# mk2.net
KiCad netlist of a schematic drawn in EAGLE
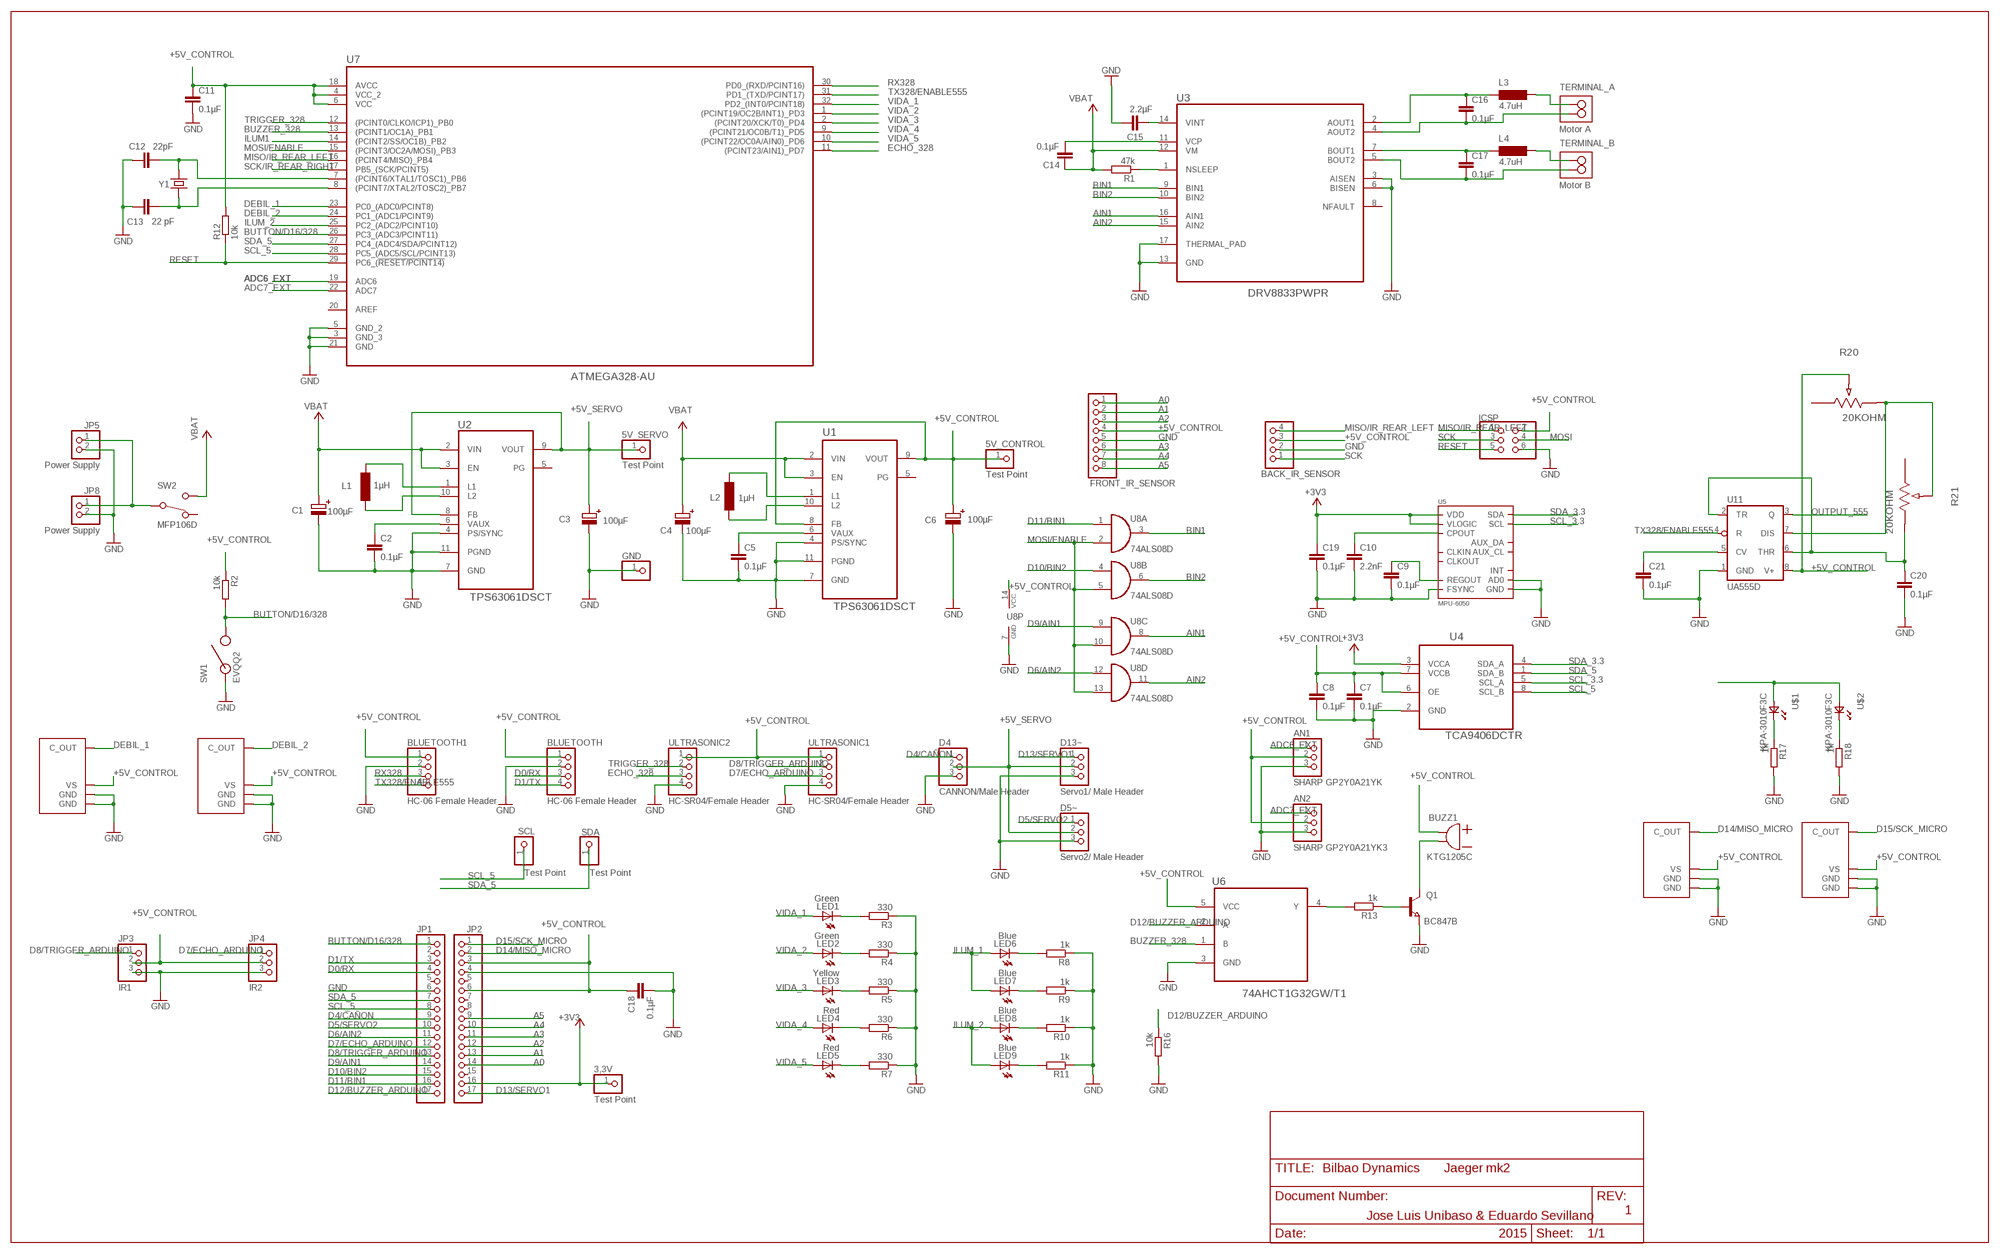
[diagram p0: schematic, sheet 1]

(export (version "E")
  (design (tool "Eeschema 10.0.6"))
  (components
    (comp (ref "3,3V")
      (value "Test Point")
      (footprint "eagle-import:1X01")
      (libsource (lib "eagle-import") (part "PINHD-1X1"))
    )
    (comp (ref "5V_CONTROL")
      (value "Test Point")
      (footprint "eagle-import:1X01")
      (libsource (lib "eagle-import") (part "PINHD-1X1"))
    )
    (comp (ref "5V_SERVO")
      (value "Test Point")
      (footprint "eagle-import:1X01")
      (libsource (lib "eagle-import") (part "PINHD-1X1"))
    )
    (comp (ref "AN1")
      (value "SHARP GP2Y0A21YK")
      (footprint "eagle-import:1X03")
      (libsource (lib "eagle-import") (part "PINHD-1X3"))
    )
    (comp (ref "AN2")
      (value "SHARP GP2Y0A21YK3")
      (footprint "eagle-import:1X03")
      (libsource (lib "eagle-import") (part "PINHD-1X3"))
    )
    (comp (ref "BACK_IR_SENSOR")
      (value "PINHD-1X4")
      (footprint "eagle-import:1X04")
      (libsource (lib "eagle-import") (part "PINHD-1X4"))
    )
    (comp (ref "BLUETOOTH")
      (value "HC-06 Female Header")
      (footprint "eagle-import:1X04")
      (libsource (lib "eagle-import") (part "PINHD-1X4"))
    )
    (comp (ref "BLUETOOTH1")
      (value "HC-06 Female Header")
      (footprint "eagle-import:1X04")
      (libsource (lib "eagle-import") (part "PINHD-1X4"))
    )
    (comp (ref "BUZZ1")
      (value "KTG1205C")
      (footprint "eagle-import:KTG1205C")
      (libsource (lib "eagle-import") (part "KTG1205C"))
    )
    (comp (ref "C1")
      (value "100µF")
      (footprint "eagle-import:EDK107M016A9G")
      (libsource (lib "eagle-import") (part "EDK107M016A9G"))
    )
    (comp (ref "C2")
      (value "0.1µF")
      (footprint "eagle-import:C0805K")
      (libsource (lib "eagle-import") (part "C-EUC0805K"))
    )
    (comp (ref "C3")
      (value "100µF")
      (footprint "eagle-import:EDK107M016A9G")
      (libsource (lib "eagle-import") (part "EDK107M016A9G"))
    )
    (comp (ref "C4")
      (value "100µF")
      (footprint "eagle-import:EDK107M016A9G")
      (libsource (lib "eagle-import") (part "EDK107M016A9G"))
    )
    (comp (ref "C5")
      (value "0.1µF")
      (footprint "eagle-import:C0805K")
      (libsource (lib "eagle-import") (part "C-EUC0805K"))
    )
    (comp (ref "C6")
      (value "100µF")
      (footprint "eagle-import:EDK107M016A9G")
      (libsource (lib "eagle-import") (part "EDK107M016A9G"))
    )
    (comp (ref "C7")
      (value "0.1µF")
      (footprint "eagle-import:C0805")
      (libsource (lib "eagle-import") (part "C-EUC0805"))
    )
    (comp (ref "C8")
      (value "0.1µF")
      (footprint "eagle-import:C0805")
      (libsource (lib "eagle-import") (part "C-EUC0805"))
    )
    (comp (ref "C9")
      (value "0.1µF")
      (footprint "eagle-import:C0805")
      (libsource (lib "eagle-import") (part "C-EUC0805"))
    )
    (comp (ref "C10")
      (value "2.2nF")
      (footprint "eagle-import:C0805")
      (libsource (lib "eagle-import") (part "C-EUC0805"))
    )
    (comp (ref "C11")
      (value "0.1µF")
      (footprint "eagle-import:C0805K")
      (libsource (lib "eagle-import") (part "C-EUC0805K"))
    )
    (comp (ref "C12")
      (value "22pF")
      (footprint "eagle-import:C0805K")
      (libsource (lib "eagle-import") (part "C-EUC0805K"))
    )
    (comp (ref "C13")
      (value "22 pF")
      (footprint "eagle-import:C0805K")
      (libsource (lib "eagle-import") (part "C-EUC0805K"))
    )
    (comp (ref "C14")
      (value "0.1µF")
      (footprint "eagle-import:C0805")
      (libsource (lib "eagle-import") (part "C-EUC0805"))
    )
    (comp (ref "C15")
      (value "2.2µF")
      (footprint "eagle-import:C0805")
      (libsource (lib "eagle-import") (part "C-EUC0805"))
    )
    (comp (ref "C16")
      (value "0.1µF")
      (footprint "eagle-import:C0805")
      (libsource (lib "eagle-import") (part "C-EUC0805"))
    )
    (comp (ref "C17")
      (value "0.1µF")
      (footprint "eagle-import:C0805")
      (libsource (lib "eagle-import") (part "C-EUC0805"))
    )
    (comp (ref "C18")
      (value "0.1µF")
      (footprint "eagle-import:C0805")
      (libsource (lib "eagle-import") (part "C-EUC0805"))
    )
    (comp (ref "C19")
      (value "0.1µF")
      (footprint "eagle-import:C0805")
      (libsource (lib "eagle-import") (part "C-EUC0805"))
    )
    (comp (ref "C20")
      (value "0.1µF")
      (footprint "eagle-import:C0805")
      (libsource (lib "eagle-import") (part "C-EUC0805"))
    )
    (comp (ref "C21")
      (value "0.1µF")
      (footprint "eagle-import:C0805")
      (libsource (lib "eagle-import") (part "C-EUC0805"))
    )
    (comp (ref "D4")
      (value "CANNON/Male Header")
      (footprint "eagle-import:1X03")
      (libsource (lib "eagle-import") (part "PINHD-1X3"))
    )
    (comp (ref "D5~")
      (value "Servo2/ Male Header")
      (footprint "eagle-import:1X03")
      (libsource (lib "eagle-import") (part "PINHD-1X3"))
    )
    (comp (ref "D13~")
      (value "Servo1/ Male Header")
      (footprint "eagle-import:1X03")
      (libsource (lib "eagle-import") (part "PINHD-1X3"))
    )
    (comp (ref "FRONT_IR_SENSOR")
      (value "PINHD-1X8")
      (footprint "eagle-import:1X08")
      (libsource (lib "eagle-import") (part "PINHD-1X8"))
    )
    (comp (ref "GND")
      (value "PINHD-1X1")
      (footprint "eagle-import:1X01")
      (libsource (lib "eagle-import") (part "PINHD-1X1"))
    )
    (comp (ref "ICSP")
      (value "PINHD-2X3")
      (footprint "eagle-import:2X03")
      (libsource (lib "eagle-import") (part "PINHD-2X3"))
    )
    (comp (ref "IR_REC1")
      (value "TSMP77000TR")
      (footprint "eagle-import:TSMP77000TR")
      (libsource (lib "eagle-import") (part "TSMP77000TR"))
    )
    (comp (ref "IR_REC2")
      (value "TSMP77000TR")
      (footprint "eagle-import:TSMP77000TR")
      (libsource (lib "eagle-import") (part "TSMP77000TR"))
    )
    (comp (ref "IR_REC3")
      (value "TSMP77000TR")
      (footprint "eagle-import:TSMP77000TR")
      (libsource (lib "eagle-import") (part "TSMP77000TR"))
    )
    (comp (ref "IR_REC4")
      (value "TSMP77000TR")
      (footprint "eagle-import:TSMP77000TR")
      (libsource (lib "eagle-import") (part "TSMP77000TR"))
    )
    (comp (ref "JP1")
      (value "PINHD-1X17")
      (footprint "eagle-import:1X17")
      (libsource (lib "eagle-import") (part "PINHD-1X17"))
    )
    (comp (ref "JP2")
      (value "PINHD-1X17")
      (footprint "eagle-import:1X17")
      (libsource (lib "eagle-import") (part "PINHD-1X17"))
    )
    (comp (ref "JP3")
      (value "IR1")
      (footprint "eagle-import:1X03")
      (libsource (lib "eagle-import") (part "PINHD-1X3"))
    )
    (comp (ref "JP4")
      (value "IR2")
      (footprint "eagle-import:1X03")
      (libsource (lib "eagle-import") (part "PINHD-1X3"))
    )
    (comp (ref "JP5")
      (value "Power Supply")
      (footprint "eagle-import:1X02")
      (libsource (lib "eagle-import") (part "PINHD-1X2"))
    )
    (comp (ref "JP8")
      (value "Power Supply")
      (footprint "eagle-import:1X02")
      (libsource (lib "eagle-import") (part "PINHD-1X2"))
    )
    (comp (ref "L1")
      (value "1µH")
      (footprint "eagle-import:MCSDRH73B")
      (libsource (lib "eagle-import") (part "MCSDRH73B"))
    )
    (comp (ref "L2")
      (value "1µH")
      (footprint "eagle-import:MCSDRH73B")
      (libsource (lib "eagle-import") (part "MCSDRH73B"))
    )
    (comp (ref "L3")
      (value "4.7uH")
      (footprint "eagle-import:SRN4012T-4R7M")
      (libsource (lib "eagle-import") (part "SRN4012T-4R7M"))
    )
    (comp (ref "L4")
      (value "4.7uH")
      (footprint "eagle-import:SRN4012T-4R7M")
      (libsource (lib "eagle-import") (part "SRN4012T-4R7M"))
    )
    (comp (ref "LED1")
      (value "Green")
      (footprint "eagle-import:SML0805")
      (libsource (lib "eagle-import") (part "LEDSML0805"))
    )
    (comp (ref "LED2")
      (value "Green")
      (footprint "eagle-import:SML0805")
      (libsource (lib "eagle-import") (part "LEDSML0805"))
    )
    (comp (ref "LED3")
      (value "Yellow")
      (footprint "eagle-import:SML0805")
      (libsource (lib "eagle-import") (part "LEDSML0805"))
    )
    (comp (ref "LED4")
      (value "Red")
      (footprint "eagle-import:SML0805")
      (libsource (lib "eagle-import") (part "LEDSML0805"))
    )
    (comp (ref "LED5")
      (value "Red")
      (footprint "eagle-import:SML0805")
      (libsource (lib "eagle-import") (part "LEDSML0805"))
    )
    (comp (ref "LED6")
      (value "Blue")
      (footprint "eagle-import:SML0805")
      (libsource (lib "eagle-import") (part "LEDSML0805"))
    )
    (comp (ref "LED7")
      (value "Blue")
      (footprint "eagle-import:SML0805")
      (libsource (lib "eagle-import") (part "LEDSML0805"))
    )
    (comp (ref "LED8")
      (value "Blue")
      (footprint "eagle-import:SML0805")
      (libsource (lib "eagle-import") (part "LEDSML0805"))
    )
    (comp (ref "LED9")
      (value "Blue")
      (footprint "eagle-import:SML0805")
      (libsource (lib "eagle-import") (part "LEDSML0805"))
    )
    (comp (ref "Q1")
      (value "BC847B")
      (footprint "eagle-import:SOT23")
      (libsource (lib "eagle-import") (part "NPN-TRANSISTOR_SOT23"))
    )
    (comp (ref "R1")
      (value "47k")
      (footprint "eagle-import:R0805")
      (libsource (lib "eagle-import") (part "R-EU_R0805"))
    )
    (comp (ref "R2")
      (value "10k")
      (footprint "eagle-import:R0805")
      (libsource (lib "eagle-import") (part "R-EU_R0805"))
    )
    (comp (ref "R3")
      (value "330")
      (footprint "eagle-import:R0805")
      (libsource (lib "eagle-import") (part "R-EU_R0805"))
    )
    (comp (ref "R4")
      (value "330")
      (footprint "eagle-import:R0805")
      (libsource (lib "eagle-import") (part "R-EU_R0805"))
    )
    (comp (ref "R5")
      (value "330")
      (footprint "eagle-import:R0805")
      (libsource (lib "eagle-import") (part "R-EU_R0805"))
    )
    (comp (ref "R6")
      (value "330")
      (footprint "eagle-import:R0805")
      (libsource (lib "eagle-import") (part "R-EU_R0805"))
    )
    (comp (ref "R7")
      (value "330")
      (footprint "eagle-import:R0805")
      (libsource (lib "eagle-import") (part "R-EU_R0805"))
    )
    (comp (ref "R8")
      (value "1k")
      (footprint "eagle-import:R0805")
      (libsource (lib "eagle-import") (part "R-EU_R0805"))
    )
    (comp (ref "R9")
      (value "1k")
      (footprint "eagle-import:R0805")
      (libsource (lib "eagle-import") (part "R-EU_R0805"))
    )
    (comp (ref "R10")
      (value "1k")
      (footprint "eagle-import:R0805")
      (libsource (lib "eagle-import") (part "R-EU_R0805"))
    )
    (comp (ref "R11")
      (value "1k")
      (footprint "eagle-import:R0805")
      (libsource (lib "eagle-import") (part "R-EU_R0805"))
    )
    (comp (ref "R12")
      (value "10k")
      (footprint "eagle-import:R0805")
      (libsource (lib "eagle-import") (part "resistor_R-EU_R0805"))
    )
    (comp (ref "R13")
      (value "1k")
      (footprint "eagle-import:R0805")
      (libsource (lib "eagle-import") (part "R-EU_R0805"))
    )
    (comp (ref "R16")
      (value "10k")
      (footprint "eagle-import:R0805")
      (libsource (lib "eagle-import") (part "R-EU_R0805"))
    )
    (comp (ref "R17")
      (value "1k")
      (footprint "eagle-import:R0805")
      (libsource (lib "eagle-import") (part "R-EU_R0805"))
    )
    (comp (ref "R18")
      (value "1k")
      (footprint "eagle-import:R0805")
      (libsource (lib "eagle-import") (part "R-EU_R0805"))
    )
    (comp (ref "R20")
      (value "20KOHM")
      (footprint "eagle-import:POT_EVM2N")
      (fields (field (name "MPN") "EVM2NSX80B24") (field (name "TOLERANCE") "±25 %"))
      (libsource (lib "eagle-import") (part "EVM-2N2NSX80B24"))
    )
    (comp (ref "R21")
      (value "20KOHM")
      (footprint "eagle-import:POT_EVM2N")
      (fields (field (name "MPN") "EVM2NSX80B24") (field (name "TOLERANCE") "±25 %"))
      (libsource (lib "eagle-import") (part "EVM-2N2NSX80B24"))
    )
    (comp (ref "SCL")
      (value "Test Point")
      (footprint "eagle-import:1X01")
      (libsource (lib "eagle-import") (part "PINHD-1X1"))
    )
    (comp (ref "SDA")
      (value "Test Point")
      (footprint "eagle-import:1X01")
      (libsource (lib "eagle-import") (part "PINHD-1X1"))
    )
    (comp (ref "SW1")
      (value "EVQQ2")
      (footprint "eagle-import:EVQQ2")
      (libsource (lib "eagle-import") (part "EVQQ2"))
    )
    (comp (ref "SW2")
      (value "MFP106D")
      (footprint "eagle-import:MFP106D")
      (libsource (lib "eagle-import") (part "MFP106D"))
    )
    (comp (ref "TERMINAL_A")
      (value "Motor A")
      (footprint "eagle-import:CTB30512BK")
      (libsource (lib "eagle-import") (part "CTB30512BK"))
    )
    (comp (ref "TERMINAL_B")
      (value "Motor B")
      (footprint "eagle-import:CTB30512BK")
      (libsource (lib "eagle-import") (part "CTB30512BK"))
    )
    (comp (ref "U$1")
      (value "KPA-3010F3C")
      (footprint "eagle-import:KPA-3010F3C")
      (libsource (lib "eagle-import") (part "KPA-3010F3C"))
    )
    (comp (ref "U$2")
      (value "KPA-3010F3C")
      (footprint "eagle-import:KPA-3010F3C")
      (libsource (lib "eagle-import") (part "KPA-3010F3C"))
    )
    (comp (ref "U1")
      (value "TPS63061DSCT")
      (footprint "eagle-import:SON50P300X300X80-11N")
      (libsource (lib "eagle-import") (part "TPS63061DSCT"))
    )
    (comp (ref "U2")
      (value "TPS63061DSCT")
      (footprint "eagle-import:SON50P300X300X80-11N")
      (libsource (lib "eagle-import") (part "TPS63061DSCT"))
    )
    (comp (ref "U3")
      (value "DRV8833PWPR")
      (footprint "eagle-import:SOP65P640X120-17N")
      (libsource (lib "eagle-import") (part "DRV8833PWPR"))
    )
    (comp (ref "U4")
      (value "TCA9406DCTR")
      (footprint "eagle-import:SOP65P400X130-8N")
      (libsource (lib "eagle-import") (part "TCA9406DCTR"))
    )
    (comp (ref "U5")
      (value "MPU-6050")
      (footprint "eagle-import:QFN.24.4X4")
      (libsource (lib "eagle-import") (part "MPU-6050"))
    )
    (comp (ref "U6")
      (value "74AHCT1G32GW/T1")
      (footprint "eagle-import:SOT65P210X110-5N")
      (libsource (lib "eagle-import") (part "74AHCT1G32GW/T1"))
    )
    (comp (ref "U7")
      (value "ATMEGA328-AU")
      (footprint "eagle-import:QFP80P900X900X120-32N")
      (libsource (lib "eagle-import") (part "ATMEGA328-AU"))
    )
    (comp (ref "U8")
      (value "74ALS08D")
      (footprint "eagle-import:SO14")
      (libsource (lib "eagle-import") (part "7408DALS"))
    )
    (comp (ref "U11")
      (value "UA555D")
      (footprint "eagle-import:SO08")
      (libsource (lib "eagle-import") (part "555DUA"))
    )
    (comp (ref "ULTRASONIC1")
      (value "HC-SR04/Female Header")
      (footprint "eagle-import:1X04")
      (libsource (lib "eagle-import") (part "PINHD-1X4"))
    )
    (comp (ref "ULTRASONIC2")
      (value "HC-SR04/Female Header")
      (footprint "eagle-import:1X04")
      (libsource (lib "eagle-import") (part "PINHD-1X4"))
    )
    (comp (ref "Y1")
      (value "E3SB16.0000F09G11AE")
      (footprint "eagle-import:E3SB16.0000F09G11A")
      (libsource (lib "eagle-import") (part "E3SB16.0000F09G11AE"))
    )
  )
  (nets
    (net (code "1") (name "+3V3") (class "Default")
      (node (ref "3,3V") (pin "1") (pinfunction "1_1") (pintype "passive"))
      (node (ref "JP2") (pin "16") (pinfunction "16_16") (pintype "passive"))
      (node (ref "U4") (pin "3") (pinfunction "VCCA_3") (pintype "power_in"))
    )
    (net (code "2") (name "/+5V_CONTROL") (class "Default")
      (node (ref "5V_CONTROL") (pin "1") (pinfunction "1_1") (pintype "passive"))
      (node (ref "AN1") (pin "2") (pinfunction "2_2") (pintype "passive"))
      (node (ref "AN2") (pin "2") (pinfunction "2_2") (pintype "passive"))
      (node (ref "BACK_IR_SENSOR") (pin "3") (pinfunction "3_3") (pintype "passive"))
      (node (ref "BLUETOOTH") (pin "1") (pinfunction "1_1") (pintype "passive"))
      (node (ref "BLUETOOTH1") (pin "1") (pinfunction "1_1") (pintype "passive"))
      (node (ref "BUZZ1") (pin "+") (pinfunction "+_+") (pintype "passive"))
      (node (ref "C11") (pin "1") (pinfunction "1_1") (pintype "passive"))
      (node (ref "C18") (pin "1") (pinfunction "1_1") (pintype "passive"))
      (node (ref "C6") (pin "1") (pinfunction "1_1") (pintype "passive"))
      (node (ref "C7") (pin "1") (pinfunction "1_1") (pintype "passive"))
      (node (ref "C8") (pin "1") (pinfunction "1_1") (pintype "passive"))
      (node (ref "FRONT_IR_SENSOR") (pin "4") (pinfunction "4_4") (pintype "passive"))
      (node (ref "ICSP") (pin "2") (pinfunction "2_2") (pintype "passive"))
      (node (ref "IR_REC1") (pin "2") (pinfunction "VS_2") (pintype "power_in"))
      (node (ref "IR_REC2") (pin "2") (pinfunction "VS_2") (pintype "power_in"))
      (node (ref "IR_REC3") (pin "2") (pinfunction "VS_2") (pintype "power_in"))
      (node (ref "IR_REC4") (pin "2") (pinfunction "VS_2") (pintype "power_in"))
      (node (ref "JP2") (pin "3") (pinfunction "3_3") (pintype "passive"))
      (node (ref "JP2") (pin "6") (pinfunction "6_6") (pintype "passive"))
      (node (ref "JP3") (pin "2") (pinfunction "2_2") (pintype "passive"))
      (node (ref "JP4") (pin "2") (pinfunction "2_2") (pintype "passive"))
      (node (ref "R12") (pin "2") (pinfunction "2_2") (pintype "passive"))
      (node (ref "R2") (pin "1") (pinfunction "1_1") (pintype "passive"))
      (node (ref "R20") (pin "2") (pinfunction "2_2") (pintype "passive"))
      (node (ref "U1") (pin "8") (pinfunction "FB_8") (pintype "input"))
      (node (ref "U1") (pin "9") (pinfunction "VOUT_9") (pintype "output"))
      (node (ref "U11") (pin "8") (pinfunction "V+_8") (pintype "power_in"))
      (node (ref "U4") (pin "6") (pinfunction "OE_6") (pintype "input"))
      (node (ref "U4") (pin "7") (pinfunction "VCCB_7") (pintype "power_in"))
      (node (ref "U6") (pin "5") (pinfunction "VCC_5") (pintype "power_in"))
      (node (ref "U7") (pin "18") (pinfunction "AVCC_18") (pintype "power_in"))
      (node (ref "U7") (pin "4") (pinfunction "VCC_2_4") (pintype "power_in"))
      (node (ref "U7") (pin "6") (pinfunction "VCC_6") (pintype "power_in"))
      (node (ref "U8") (pin "14") (pinfunction "VCC_14") (pintype "power_in"))
      (node (ref "ULTRASONIC1") (pin "1") (pinfunction "1_1") (pintype "passive"))
      (node (ref "ULTRASONIC2") (pin "1") (pinfunction "1_1") (pintype "passive"))
    )
    (net (code "3") (name "/+5V_SERVO") (class "Default")
      (node (ref "5V_SERVO") (pin "1") (pinfunction "1_1") (pintype "passive"))
      (node (ref "C3") (pin "1") (pinfunction "1_1") (pintype "passive"))
      (node (ref "D13~") (pin "2") (pinfunction "2_2") (pintype "passive"))
      (node (ref "D4") (pin "2") (pinfunction "2_2") (pintype "passive"))
      (node (ref "D5~") (pin "2") (pinfunction "2_2") (pintype "passive"))
      (node (ref "U2") (pin "8") (pinfunction "FB_8") (pintype "input"))
      (node (ref "U2") (pin "9") (pinfunction "VOUT_9") (pintype "output"))
    )
    (net (code "4") (name "/A0") (class "Default")
      (node (ref "FRONT_IR_SENSOR") (pin "1") (pinfunction "1_1") (pintype "passive"))
      (node (ref "JP2") (pin "14") (pinfunction "14_14") (pintype "passive"))
    )
    (net (code "5") (name "/A1") (class "Default")
      (node (ref "FRONT_IR_SENSOR") (pin "2") (pinfunction "2_2") (pintype "passive"))
      (node (ref "JP2") (pin "13") (pinfunction "13_13") (pintype "passive"))
    )
    (net (code "6") (name "/A2") (class "Default")
      (node (ref "FRONT_IR_SENSOR") (pin "3") (pinfunction "3_3") (pintype "passive"))
      (node (ref "JP2") (pin "12") (pinfunction "12_12") (pintype "passive"))
    )
    (net (code "7") (name "/A3") (class "Default")
      (node (ref "FRONT_IR_SENSOR") (pin "6") (pinfunction "6_6") (pintype "passive"))
      (node (ref "JP2") (pin "11") (pinfunction "11_11") (pintype "passive"))
    )
    (net (code "8") (name "/A4") (class "Default")
      (node (ref "FRONT_IR_SENSOR") (pin "7") (pinfunction "7_7") (pintype "passive"))
      (node (ref "JP2") (pin "10") (pinfunction "10_10") (pintype "passive"))
    )
    (net (code "9") (name "/A5") (class "Default")
      (node (ref "FRONT_IR_SENSOR") (pin "8") (pinfunction "8_8") (pintype "passive"))
      (node (ref "JP2") (pin "9") (pinfunction "9_9") (pintype "passive"))
    )
    (net (code "10") (name "/ADC6_EXT") (class "Default")
      (node (ref "AN1") (pin "1") (pinfunction "1_1") (pintype "passive"))
      (node (ref "U7") (pin "19") (pinfunction "ADC6_19") (pintype "input"))
    )
    (net (code "11") (name "/ADC7_EXT") (class "Default")
      (node (ref "AN2") (pin "1") (pinfunction "1_1") (pintype "passive"))
      (node (ref "U7") (pin "22") (pinfunction "ADC7_22") (pintype "input"))
    )
    (net (code "12") (name "/AIN1") (class "Default")
      (node (ref "U3") (pin "16") (pinfunction "AIN1_16") (pintype "input"))
      (node (ref "U8") (pin "8") (pinfunction "O_8") (pintype "output"))
    )
    (net (code "13") (name "/AIN2") (class "Default")
      (node (ref "U3") (pin "15") (pinfunction "AIN2_15") (pintype "input"))
      (node (ref "U8") (pin "11") (pinfunction "O_11") (pintype "output"))
    )
    (net (code "14") (name "/BIN1") (class "Default")
      (node (ref "U3") (pin "9") (pinfunction "BIN1_9") (pintype "input"))
      (node (ref "U8") (pin "3") (pinfunction "O_3") (pintype "output"))
    )
    (net (code "15") (name "/BIN2") (class "Default")
      (node (ref "U3") (pin "10") (pinfunction "BIN2_10") (pintype "input"))
      (node (ref "U8") (pin "6") (pinfunction "O_6") (pintype "output"))
    )
    (net (code "16") (name "/BUTTON{slash}D16{slash}328") (class "Default")
      (node (ref "JP1") (pin "1") (pinfunction "1_1") (pintype "passive"))
      (node (ref "R2") (pin "2") (pinfunction "2_2") (pintype "passive"))
      (node (ref "SW1") (pin "P$1") (pinfunction "P$2_P$1") (pintype "passive"))
      (node (ref "SW1") (pin "P$4") (pinfunction "P$2_P$4") (pintype "passive"))
      (node (ref "U7") (pin "26") (pinfunction "PC3_(ADC3/PCINT11)_26") (pintype "bidirectional"))
    )
    (net (code "17") (name "/BUZZER_328") (class "Default")
      (node (ref "U6") (pin "1") (pinfunction "B_1") (pintype "input"))
      (node (ref "U7") (pin "13") (pinfunction "(PCINT1/OC1A)_PB1_13") (pintype "bidirectional"))
    )
    (net (code "18") (name "/D0{slash}RX") (class "Default")
      (node (ref "BLUETOOTH") (pin "3") (pinfunction "3_3") (pintype "passive"))
      (node (ref "JP1") (pin "4") (pinfunction "4_4") (pintype "passive"))
    )
    (net (code "19") (name "/D1{slash}TX") (class "Default")
      (node (ref "BLUETOOTH") (pin "4") (pinfunction "4_4") (pintype "passive"))
      (node (ref "JP1") (pin "3") (pinfunction "3_3") (pintype "passive"))
    )
    (net (code "20") (name "/D4{slash}CAÑON") (class "Default")
      (node (ref "D4") (pin "1") (pinfunction "1_1") (pintype "passive"))
      (node (ref "JP1") (pin "9") (pinfunction "9_9") (pintype "passive"))
    )
    (net (code "21") (name "/D5{slash}SERVO2") (class "Default")
      (node (ref "D5~") (pin "1") (pinfunction "1_1") (pintype "passive"))
      (node (ref "JP1") (pin "10") (pinfunction "10_10") (pintype "passive"))
    )
    (net (code "22") (name "/D6{slash}AIN2") (class "Default")
      (node (ref "JP1") (pin "11") (pinfunction "11_11") (pintype "passive"))
      (node (ref "U8") (pin "12") (pinfunction "I0_12") (pintype "input"))
    )
    (net (code "23") (name "/D7{slash}ECHO_ARDUINO") (class "Default")
      (node (ref "JP1") (pin "12") (pinfunction "12_12") (pintype "passive"))
      (node (ref "JP4") (pin "1") (pinfunction "1_1") (pintype "passive"))
      (node (ref "ULTRASONIC1") (pin "3") (pinfunction "3_3") (pintype "passive"))
    )
    (net (code "24") (name "/D8{slash}TRIGGER_ARDUINO") (class "Default")
      (node (ref "JP1") (pin "13") (pinfunction "13_13") (pintype "passive"))
      (node (ref "JP3") (pin "1") (pinfunction "1_1") (pintype "passive"))
      (node (ref "ULTRASONIC1") (pin "2") (pinfunction "2_2") (pintype "passive"))
    )
    (net (code "25") (name "/D9{slash}AIN1") (class "Default")
      (node (ref "JP1") (pin "14") (pinfunction "14_14") (pintype "passive"))
      (node (ref "U8") (pin "9") (pinfunction "I0_9") (pintype "input"))
    )
    (net (code "26") (name "/D10{slash}BIN2") (class "Default")
      (node (ref "JP1") (pin "15") (pinfunction "15_15") (pintype "passive"))
      (node (ref "U8") (pin "4") (pinfunction "I0_4") (pintype "input"))
    )
    (net (code "27") (name "/D11{slash}BIN1") (class "Default")
      (node (ref "JP1") (pin "16") (pinfunction "16_16") (pintype "passive"))
      (node (ref "U8") (pin "1") (pinfunction "I0_1") (pintype "input"))
    )
    (net (code "28") (name "/D12{slash}BUZZER_ARDUINO") (class "Default")
      (node (ref "JP1") (pin "17") (pinfunction "17_17") (pintype "passive"))
      (node (ref "R16") (pin "1") (pinfunction "1_1") (pintype "passive"))
      (node (ref "U6") (pin "2") (pinfunction "A_2") (pintype "input"))
    )
    (net (code "29") (name "/D13{slash}SERVO1") (class "Default")
      (node (ref "D13~") (pin "1") (pinfunction "1_1") (pintype "passive"))
      (node (ref "JP2") (pin "17") (pinfunction "17_17") (pintype "passive"))
    )
    (net (code "30") (name "/D14{slash}MISO_MICRO") (class "Default")
      (node (ref "IR_REC1") (pin "3") (pinfunction "C_OUT_3") (pintype "bidirectional"))
      (node (ref "JP2") (pin "2") (pinfunction "2_2") (pintype "passive"))
    )
    (net (code "31") (name "/D15{slash}SCK_MICRO") (class "Default")
      (node (ref "IR_REC2") (pin "3") (pinfunction "C_OUT_3") (pintype "bidirectional"))
      (node (ref "JP2") (pin "1") (pinfunction "1_1") (pintype "passive"))
    )
    (net (code "32") (name "/DEBIL_1") (class "Default")
      (node (ref "IR_REC3") (pin "3") (pinfunction "C_OUT_3") (pintype "bidirectional"))
      (node (ref "U7") (pin "23") (pinfunction "PC0_(ADC0/PCINT8)_23") (pintype "bidirectional"))
    )
    (net (code "33") (name "/DEBIL_2") (class "Default")
      (node (ref "IR_REC4") (pin "3") (pinfunction "C_OUT_3") (pintype "bidirectional"))
      (node (ref "U7") (pin "24") (pinfunction "PC1_(ADC1/PCINT9)_24") (pintype "bidirectional"))
    )
    (net (code "34") (name "/ECHO_328") (class "Default")
      (node (ref "U7") (pin "11") (pinfunction "(PCINT23/AIN1)_PD7_11") (pintype "bidirectional"))
      (node (ref "ULTRASONIC2") (pin "3") (pinfunction "3_3") (pintype "passive"))
    )
    (net (code "35") (name "/ILUM1") (class "Default")
      (node (ref "U7") (pin "14") (pinfunction "(PCINT2/SS/OC1B)_PB2_14") (pintype "bidirectional"))
    )
    (net (code "36") (name "/ILUM_1") (class "Default")
      (node (ref "LED6") (pin "A") (pinfunction "A_A") (pintype "passive"))
      (node (ref "LED7") (pin "A") (pinfunction "A_A") (pintype "passive"))
    )
    (net (code "37") (name "/ILUM_2") (class "Default")
      (node (ref "LED8") (pin "A") (pinfunction "A_A") (pintype "passive"))
      (node (ref "LED9") (pin "A") (pinfunction "A_A") (pintype "passive"))
      (node (ref "U7") (pin "25") (pinfunction "PC2_(ADC2/PCINT10)_25") (pintype "bidirectional"))
    )
    (net (code "38") (name "/MISO{slash}IR_REAR_LEFT") (class "Default")
      (node (ref "BACK_IR_SENSOR") (pin "4") (pinfunction "4_4") (pintype "passive"))
      (node (ref "ICSP") (pin "1") (pinfunction "1_1") (pintype "passive"))
      (node (ref "U7") (pin "16") (pinfunction "(PCINT4/MISO)_PB4_16") (pintype "bidirectional"))
    )
    (net (code "39") (name "/MOSI") (class "Default")
      (node (ref "ICSP") (pin "4") (pinfunction "4_4") (pintype "passive"))
    )
    (net (code "40") (name "/MOSI{slash}ENABLE") (class "Default")
      (node (ref "U7") (pin "15") (pinfunction "(PCINT3/OC2A/MOSI)_PB3_15") (pintype "bidirectional"))
      (node (ref "U8") (pin "10") (pinfunction "I1_10") (pintype "input"))
      (node (ref "U8") (pin "13") (pinfunction "I1_13") (pintype "input"))
      (node (ref "U8") (pin "2") (pinfunction "I1_2") (pintype "input"))
      (node (ref "U8") (pin "5") (pinfunction "I1_5") (pintype "input"))
    )
    (net (code "41") (name "/OUTPUT_555") (class "Default")
      (node (ref "U$1") (pin "A") (pinfunction "A_A") (pintype "passive"))
      (node (ref "U$2") (pin "A") (pinfunction "A_A") (pintype "passive"))
      (node (ref "U11") (pin "3") (pinfunction "Q_3") (pintype "output"))
    )
    (net (code "42") (name "/RESET") (class "Default")
      (node (ref "ICSP") (pin "5") (pinfunction "5_5") (pintype "passive"))
      (node (ref "R12") (pin "1") (pinfunction "1_1") (pintype "passive"))
      (node (ref "U7") (pin "29") (pinfunction "PC6_(~{RESET/PCINT14})_29") (pintype "bidirectional"))
    )
    (net (code "43") (name "/RX328") (class "Default")
      (node (ref "BLUETOOTH1") (pin "3") (pinfunction "3_3") (pintype "passive"))
      (node (ref "U7") (pin "30") (pinfunction "PD0_(RXD/PCINT16)_30") (pintype "bidirectional"))
    )
    (net (code "44") (name "/SCK") (class "Default")
      (node (ref "BACK_IR_SENSOR") (pin "1") (pinfunction "1_1") (pintype "passive"))
      (node (ref "ICSP") (pin "3") (pinfunction "3_3") (pintype "passive"))
    )
    (net (code "45") (name "/SCK{slash}IR_REAR_RIGHT") (class "Default")
      (node (ref "U7") (pin "17") (pinfunction "PB5_(SCK/PCINT5)_17") (pintype "bidirectional"))
    )
    (net (code "46") (name "/SCL_3.3") (class "Default")
      (node (ref "U4") (pin "5") (pinfunction "SCL_A_5") (pintype "bidirectional"))
      (node (ref "U5") (pin "23") (pinfunction "SCL_23") (pintype "bidirectional"))
    )
    (net (code "47") (name "/SCL_5") (class "Default")
      (node (ref "JP1") (pin "8") (pinfunction "8_8") (pintype "passive"))
      (node (ref "SCL") (pin "1") (pinfunction "1_1") (pintype "passive"))
      (node (ref "U4") (pin "8") (pinfunction "SCL_B_8") (pintype "bidirectional"))
      (node (ref "U7") (pin "28") (pinfunction "PC5_(ADC5/SCL/PCINT13)_28") (pintype "bidirectional"))
    )
    (net (code "48") (name "/SDA_3.3") (class "Default")
      (node (ref "U4") (pin "4") (pinfunction "SDA_A_4") (pintype "bidirectional"))
      (node (ref "U5") (pin "24") (pinfunction "SDA_24") (pintype "bidirectional"))
    )
    (net (code "49") (name "/SDA_5") (class "Default")
      (node (ref "JP1") (pin "7") (pinfunction "7_7") (pintype "passive"))
      (node (ref "SDA") (pin "1") (pinfunction "1_1") (pintype "passive"))
      (node (ref "U4") (pin "1") (pinfunction "SDA_B_1") (pintype "bidirectional"))
      (node (ref "U7") (pin "27") (pinfunction "PC4_(ADC4/SDA/PCINT12)_27") (pintype "bidirectional"))
    )
    (net (code "50") (name "/TRIGGER_328") (class "Default")
      (node (ref "U7") (pin "12") (pinfunction "(PCINT0/CLKO/ICP1)_PB0_12") (pintype "bidirectional"))
      (node (ref "ULTRASONIC2") (pin "2") (pinfunction "2_2") (pintype "passive"))
    )
    (net (code "51") (name "/TX328{slash}ENABLE555") (class "Default")
      (node (ref "BLUETOOTH1") (pin "4") (pinfunction "4_4") (pintype "passive"))
      (node (ref "U11") (pin "4") (pinfunction "R_4") (pintype "input"))
      (node (ref "U7") (pin "31") (pinfunction "PD1_(TXD/PCINT17)_31") (pintype "bidirectional"))
    )
    (net (code "52") (name "/VIDA_1") (class "Default")
      (node (ref "LED1") (pin "A") (pinfunction "A_A") (pintype "passive"))
      (node (ref "U7") (pin "32") (pinfunction "PD2_(INT0/PCINT18)_32") (pintype "bidirectional"))
    )
    (net (code "53") (name "/VIDA_2") (class "Default")
      (node (ref "LED2") (pin "A") (pinfunction "A_A") (pintype "passive"))
      (node (ref "U7") (pin "1") (pinfunction "(PCINT19/OC2B/INT1)_PD3_1") (pintype "bidirectional"))
    )
    (net (code "54") (name "/VIDA_3") (class "Default")
      (node (ref "LED3") (pin "A") (pinfunction "A_A") (pintype "passive"))
      (node (ref "U7") (pin "2") (pinfunction "(PCINT20/XCK/T0)_PD4_2") (pintype "bidirectional"))
    )
    (net (code "55") (name "/VIDA_4") (class "Default")
      (node (ref "LED4") (pin "A") (pinfunction "A_A") (pintype "passive"))
      (node (ref "U7") (pin "9") (pinfunction "(PCINT21/OC0B/T1)_PD5_9") (pintype "bidirectional"))
    )
    (net (code "56") (name "/VIDA_5") (class "Default")
      (node (ref "LED5") (pin "A") (pinfunction "A_A") (pintype "passive"))
      (node (ref "U7") (pin "10") (pinfunction "(PCINT22/OC0A/AIN0)_PD6_10") (pintype "bidirectional"))
    )
    (net (code "57") (name "GND") (class "Default")
      (node (ref "AN1") (pin "3") (pinfunction "3_3") (pintype "passive"))
      (node (ref "AN2") (pin "3") (pinfunction "3_3") (pintype "passive"))
      (node (ref "BACK_IR_SENSOR") (pin "2") (pinfunction "2_2") (pintype "passive"))
      (node (ref "BLUETOOTH") (pin "2") (pinfunction "2_2") (pintype "passive"))
      (node (ref "BLUETOOTH1") (pin "2") (pinfunction "2_2") (pintype "passive"))
      (node (ref "C1") (pin "2") (pinfunction "2_2") (pintype "passive"))
      (node (ref "C10") (pin "2") (pinfunction "2_2") (pintype "passive"))
      (node (ref "C11") (pin "2") (pinfunction "2_2") (pintype "passive"))
      (node (ref "C12") (pin "1") (pinfunction "1_1") (pintype "passive"))
      (node (ref "C13") (pin "1") (pinfunction "1_1") (pintype "passive"))
      (node (ref "C15") (pin "1") (pinfunction "1_1") (pintype "passive"))
      (node (ref "C18") (pin "2") (pinfunction "2_2") (pintype "passive"))
      (node (ref "C19") (pin "2") (pinfunction "2_2") (pintype "passive"))
      (node (ref "C2") (pin "2") (pinfunction "2_2") (pintype "passive"))
      (node (ref "C20") (pin "2") (pinfunction "2_2") (pintype "passive"))
      (node (ref "C21") (pin "2") (pinfunction "2_2") (pintype "passive"))
      (node (ref "C3") (pin "2") (pinfunction "2_2") (pintype "passive"))
      (node (ref "C4") (pin "2") (pinfunction "2_2") (pintype "passive"))
      (node (ref "C5") (pin "2") (pinfunction "2_2") (pintype "passive"))
      (node (ref "C6") (pin "2") (pinfunction "2_2") (pintype "passive"))
      (node (ref "C7") (pin "2") (pinfunction "2_2") (pintype "passive"))
      (node (ref "C8") (pin "2") (pinfunction "2_2") (pintype "passive"))
      (node (ref "C9") (pin "2") (pinfunction "2_2") (pintype "passive"))
      (node (ref "D13~") (pin "3") (pinfunction "3_3") (pintype "passive"))
      (node (ref "D4") (pin "3") (pinfunction "3_3") (pintype "passive"))
      (node (ref "D5~") (pin "3") (pinfunction "3_3") (pintype "passive"))
      (node (ref "FRONT_IR_SENSOR") (pin "5") (pinfunction "5_5") (pintype "passive"))
      (node (ref "GND") (pin "1") (pinfunction "1_1") (pintype "passive"))
      (node (ref "ICSP") (pin "6") (pinfunction "6_6") (pintype "passive"))
      (node (ref "IR_REC1") (pin "1") (pinfunction "GND_1") (pintype "power_in"))
      (node (ref "IR_REC1") (pin "4") (pinfunction "GND_4") (pintype "power_in"))
      (node (ref "IR_REC2") (pin "1") (pinfunction "GND_1") (pintype "power_in"))
      (node (ref "IR_REC2") (pin "4") (pinfunction "GND_4") (pintype "power_in"))
      (node (ref "IR_REC3") (pin "1") (pinfunction "GND_1") (pintype "power_in"))
      (node (ref "IR_REC3") (pin "4") (pinfunction "GND_4") (pintype "power_in"))
      (node (ref "IR_REC4") (pin "1") (pinfunction "GND_1") (pintype "power_in"))
      (node (ref "IR_REC4") (pin "4") (pinfunction "GND_4") (pintype "power_in"))
      (node (ref "JP1") (pin "6") (pinfunction "6_6") (pintype "passive"))
      (node (ref "JP2") (pin "4") (pinfunction "4_4") (pintype "passive"))
      (node (ref "JP3") (pin "3") (pinfunction "3_3") (pintype "passive"))
      (node (ref "JP4") (pin "3") (pinfunction "3_3") (pintype "passive"))
      (node (ref "JP5") (pin "2") (pinfunction "2_2") (pintype "passive"))
      (node (ref "JP8") (pin "2") (pinfunction "2_2") (pintype "passive"))
      (node (ref "Q1") (pin "2") (pinfunction "E_2") (pintype "passive"))
      (node (ref "R10") (pin "1") (pinfunction "1_1") (pintype "passive"))
      (node (ref "R11") (pin "1") (pinfunction "1_1") (pintype "passive"))
      (node (ref "R16") (pin "2") (pinfunction "2_2") (pintype "passive"))
      (node (ref "R17") (pin "2") (pinfunction "2_2") (pintype "passive"))
      (node (ref "R18") (pin "2") (pinfunction "2_2") (pintype "passive"))
      (node (ref "R3") (pin "1") (pinfunction "1_1") (pintype "passive"))
      (node (ref "R4") (pin "1") (pinfunction "1_1") (pintype "passive"))
      (node (ref "R5") (pin "1") (pinfunction "1_1") (pintype "passive"))
      (node (ref "R6") (pin "1") (pinfunction "1_1") (pintype "passive"))
      (node (ref "R7") (pin "1") (pinfunction "1_1") (pintype "passive"))
      (node (ref "R8") (pin "1") (pinfunction "1_1") (pintype "passive"))
      (node (ref "R9") (pin "1") (pinfunction "1_1") (pintype "passive"))
      (node (ref "SW1") (pin "P$2") (pinfunction "P$1_P$2") (pintype "passive"))
      (node (ref "SW1") (pin "P$3") (pinfunction "P$1_P$3") (pintype "passive"))
      (node (ref "U1") (pin "11") (pinfunction "PGND_11") (pintype "passive"))
      (node (ref "U1") (pin "4") (pinfunction "PS/SYNC_4") (pintype "input"))
      (node (ref "U1") (pin "7") (pinfunction "GND_7") (pintype "passive"))
      (node (ref "U11") (pin "1") (pinfunction "GND_1") (pintype "power_in"))
      (node (ref "U2") (pin "11") (pinfunction "PGND_11") (pintype "passive"))
      (node (ref "U2") (pin "4") (pinfunction "PS/SYNC_4") (pintype "input"))
      (node (ref "U2") (pin "7") (pinfunction "GND_7") (pintype "passive"))
      (node (ref "U3") (pin "13") (pinfunction "GND_13") (pintype "passive"))
      (node (ref "U3") (pin "17") (pinfunction "THERMAL_PAD_17") (pintype "passive"))
      (node (ref "U3") (pin "3") (pinfunction "AISEN_3") (pintype "bidirectional"))
      (node (ref "U3") (pin "6") (pinfunction "BISEN_6") (pintype "bidirectional"))
      (node (ref "U4") (pin "2") (pinfunction "GND_2") (pintype "power_in"))
      (node (ref "U5") (pin "11") (pinfunction "FSYNC_11") (pintype "bidirectional"))
      (node (ref "U5") (pin "18") (pinfunction "GND_18") (pintype "bidirectional"))
      (node (ref "U5") (pin "9") (pinfunction "AD0_9") (pintype "bidirectional"))
      (node (ref "U6") (pin "3") (pinfunction "GND_3") (pintype "passive"))
      (node (ref "U7") (pin "21") (pinfunction "GND_21") (pintype "passive"))
      (node (ref "U7") (pin "3") (pinfunction "GND_3_3") (pintype "passive"))
      (node (ref "U7") (pin "5") (pinfunction "GND_2_5") (pintype "passive"))
      (node (ref "U8") (pin "7") (pinfunction "GND_7") (pintype "power_in"))
      (node (ref "ULTRASONIC1") (pin "4") (pinfunction "4_4") (pintype "passive"))
      (node (ref "ULTRASONIC2") (pin "4") (pinfunction "4_4") (pintype "passive"))
    )
    (net (code "58") (name "Net-(JP5-Pad1)") (class "Default")
      (node (ref "JP5") (pin "1") (pinfunction "1_1") (pintype "passive"))
      (node (ref "JP8") (pin "1") (pinfunction "1_1") (pintype "passive"))
      (node (ref "SW2") (pin "COM") (pinfunction "COM_COM") (pintype "passive"))
    )
    (net (code "59") (name "Net-(L1-P$1)") (class "Default")
      (node (ref "L1") (pin "1") (pinfunction "P$1_1") (pintype "passive"))
      (node (ref "U2") (pin "10") (pinfunction "L2_10") (pintype "input"))
    )
    (net (code "60") (name "Net-(L1-P$2)") (class "Default")
      (node (ref "L1") (pin "2") (pinfunction "P$2_2") (pintype "passive"))
      (node (ref "U2") (pin "1") (pinfunction "L1_1") (pintype "input"))
    )
    (net (code "61") (name "Net-(L2-P$1)") (class "Default")
      (node (ref "L2") (pin "1") (pinfunction "P$1_1") (pintype "passive"))
      (node (ref "U1") (pin "10") (pinfunction "L2_10") (pintype "input"))
    )
    (net (code "62") (name "Net-(L2-P$2)") (class "Default")
      (node (ref "L2") (pin "2") (pinfunction "P$2_2") (pintype "passive"))
      (node (ref "U1") (pin "1") (pinfunction "L1_1") (pintype "input"))
    )
    (net (code "63") (name "Net-(L3-PadP$2)") (class "Default")
      (node (ref "L3") (pin "P$2") (pinfunction "P$2_P$2") (pintype "passive"))
      (node (ref "TERMINAL_A") (pin "1") (pinfunction "1_1") (pintype "passive"))
    )
    (net (code "64") (name "Net-(L4-PadP$2)") (class "Default")
      (node (ref "L4") (pin "P$2") (pinfunction "P$2_P$2") (pintype "passive"))
      (node (ref "TERMINAL_B") (pin "1") (pinfunction "1_1") (pintype "passive"))
    )
    (net (code "65") (name "Net-(LED1-PadC)") (class "Default")
      (node (ref "LED1") (pin "C") (pinfunction "C_C") (pintype "passive"))
      (node (ref "R3") (pin "2") (pinfunction "2_2") (pintype "passive"))
    )
    (net (code "66") (name "Net-(LED2-PadC)") (class "Default")
      (node (ref "LED2") (pin "C") (pinfunction "C_C") (pintype "passive"))
      (node (ref "R4") (pin "2") (pinfunction "2_2") (pintype "passive"))
    )
    (net (code "67") (name "Net-(LED3-PadC)") (class "Default")
      (node (ref "LED3") (pin "C") (pinfunction "C_C") (pintype "passive"))
      (node (ref "R5") (pin "2") (pinfunction "2_2") (pintype "passive"))
    )
    (net (code "68") (name "Net-(LED4-PadC)") (class "Default")
      (node (ref "LED4") (pin "C") (pinfunction "C_C") (pintype "passive"))
      (node (ref "R6") (pin "2") (pinfunction "2_2") (pintype "passive"))
    )
    (net (code "69") (name "Net-(LED5-PadC)") (class "Default")
      (node (ref "LED5") (pin "C") (pinfunction "C_C") (pintype "passive"))
      (node (ref "R7") (pin "2") (pinfunction "2_2") (pintype "passive"))
    )
    (net (code "70") (name "Net-(LED6-PadC)") (class "Default")
      (node (ref "LED6") (pin "C") (pinfunction "C_C") (pintype "passive"))
      (node (ref "R8") (pin "2") (pinfunction "2_2") (pintype "passive"))
    )
    (net (code "71") (name "Net-(LED7-PadC)") (class "Default")
      (node (ref "LED7") (pin "C") (pinfunction "C_C") (pintype "passive"))
      (node (ref "R9") (pin "2") (pinfunction "2_2") (pintype "passive"))
    )
    (net (code "72") (name "Net-(LED8-PadC)") (class "Default")
      (node (ref "LED8") (pin "C") (pinfunction "C_C") (pintype "passive"))
      (node (ref "R10") (pin "2") (pinfunction "2_2") (pintype "passive"))
    )
    (net (code "73") (name "Net-(LED9-PadC)") (class "Default")
      (node (ref "LED9") (pin "C") (pinfunction "C_C") (pintype "passive"))
      (node (ref "R11") (pin "2") (pinfunction "2_2") (pintype "passive"))
    )
    (net (code "74") (name "Net-(Q1-B)") (class "Default")
      (node (ref "Q1") (pin "1") (pinfunction "B_1") (pintype "passive"))
      (node (ref "R13") (pin "1") (pinfunction "1_1") (pintype "passive"))
    )
    (net (code "75") (name "Net-(Q1-C)") (class "Default")
      (node (ref "BUZZ1") (pin "-") (pinfunction "-_-") (pintype "passive"))
      (node (ref "Q1") (pin "3") (pinfunction "C_3") (pintype "passive"))
    )
    (net (code "76") (name "Net-(R17-Pad1)") (class "Default")
      (node (ref "R17") (pin "1") (pinfunction "1_1") (pintype "passive"))
      (node (ref "U$1") (pin "C") (pinfunction "C_C") (pintype "passive"))
    )
    (net (code "77") (name "Net-(R18-Pad1)") (class "Default")
      (node (ref "R18") (pin "1") (pinfunction "1_1") (pintype "passive"))
      (node (ref "U$2") (pin "C") (pinfunction "C_C") (pintype "passive"))
    )
    (net (code "78") (name "Net-(U1-VAUX)") (class "Default")
      (node (ref "C5") (pin "1") (pinfunction "1_1") (pintype "passive"))
      (node (ref "U1") (pin "6") (pinfunction "VAUX_6") (pintype "passive"))
    )
    (net (code "79") (name "Net-(U2-VAUX)") (class "Default")
      (node (ref "C2") (pin "1") (pinfunction "1_1") (pintype "passive"))
      (node (ref "U2") (pin "6") (pinfunction "VAUX_6") (pintype "passive"))
    )
    (net (code "80") (name "Net-(U3-AOUT1)") (class "Default")
      (node (ref "C16") (pin "1") (pinfunction "1_1") (pintype "passive"))
      (node (ref "L3") (pin "P$1") (pinfunction "P$1_P$1") (pintype "passive"))
      (node (ref "U3") (pin "2") (pinfunction "AOUT1_2") (pintype "output"))
    )
    (net (code "81") (name "Net-(U3-AOUT2)") (class "Default")
      (node (ref "C16") (pin "2") (pinfunction "2_2") (pintype "passive"))
      (node (ref "TERMINAL_A") (pin "2") (pinfunction "2_2") (pintype "passive"))
      (node (ref "U3") (pin "4") (pinfunction "AOUT2_4") (pintype "output"))
    )
    (net (code "82") (name "Net-(U3-BOUT1)") (class "Default")
      (node (ref "C17") (pin "1") (pinfunction "1_1") (pintype "passive"))
      (node (ref "L4") (pin "P$1") (pinfunction "P$1_P$1") (pintype "passive"))
      (node (ref "U3") (pin "7") (pinfunction "BOUT1_7") (pintype "output"))
    )
    (net (code "83") (name "Net-(U3-BOUT2)") (class "Default")
      (node (ref "C17") (pin "2") (pinfunction "2_2") (pintype "passive"))
      (node (ref "TERMINAL_B") (pin "2") (pinfunction "2_2") (pintype "passive"))
      (node (ref "U3") (pin "5") (pinfunction "BOUT2_5") (pintype "output"))
    )
    (net (code "84") (name "Net-(U3-NSLEEP)") (class "Default")
      (node (ref "R1") (pin "1") (pinfunction "1_1") (pintype "passive"))
      (node (ref "U3") (pin "1") (pinfunction "NSLEEP_1") (pintype "input"))
    )
    (net (code "85") (name "Net-(U3-VCP)") (class "Default")
      (node (ref "C14") (pin "2") (pinfunction "2_2") (pintype "passive"))
      (node (ref "U3") (pin "11") (pinfunction "VCP_11") (pintype "bidirectional"))
    )
    (net (code "86") (name "Net-(U3-VINT)") (class "Default")
      (node (ref "C15") (pin "2") (pinfunction "2_2") (pintype "passive"))
      (node (ref "U3") (pin "14") (pinfunction "VINT_14") (pintype "power_in"))
    )
    (net (code "87") (name "Net-(U5-CPOUT)") (class "Default")
      (node (ref "C10") (pin "1") (pinfunction "1_1") (pintype "passive"))
      (node (ref "U5") (pin "20") (pinfunction "CPOUT_20") (pintype "bidirectional"))
    )
    (net (code "88") (name "Net-(U5-REGOUT)") (class "Default")
      (node (ref "C9") (pin "1") (pinfunction "1_1") (pintype "passive"))
      (node (ref "U5") (pin "10") (pinfunction "REGOUT_10") (pintype "bidirectional"))
    )
    (net (code "89") (name "Net-(U5-VDD)") (class "Default")
      (node (ref "C19") (pin "1") (pinfunction "1_1") (pintype "passive"))
      (node (ref "U5") (pin "13") (pinfunction "VDD_13") (pintype "bidirectional"))
      (node (ref "U5") (pin "8") (pinfunction "VLOGIC_8") (pintype "bidirectional"))
    )
    (net (code "90") (name "Net-(U6-Y)") (class "Default")
      (node (ref "R13") (pin "2") (pinfunction "2_2") (pintype "passive"))
      (node (ref "U6") (pin "4") (pinfunction "Y_4") (pintype "output"))
    )
    (net (code "91") (name "Net-(U7-(PCINT6{slash}XTAL1{slash}TOSC1)_PB6)") (class "Default")
      (node (ref "C12") (pin "2") (pinfunction "2_2") (pintype "passive"))
      (node (ref "U7") (pin "7") (pinfunction "(PCINT6/XTAL1/TOSC1)_PB6_7") (pintype "bidirectional"))
      (node (ref "Y1") (pin "2") (pinfunction "P$2_2") (pintype "passive"))
    )
    (net (code "92") (name "Net-(U7-(PCINT7{slash}XTAL2{slash}TOSC2)_PB7)") (class "Default")
      (node (ref "C13") (pin "2") (pinfunction "2_2") (pintype "passive"))
      (node (ref "U7") (pin "8") (pinfunction "(PCINT7/XTAL2/TOSC2)_PB7_8") (pintype "bidirectional"))
      (node (ref "Y1") (pin "1") (pinfunction "P$1_1") (pintype "passive"))
    )
    (net (code "93") (name "Net-(U11-CV)") (class "Default")
      (node (ref "C21") (pin "1") (pinfunction "1_1") (pintype "passive"))
      (node (ref "U11") (pin "5") (pinfunction "CV_5") (pintype "input"))
    )
    (net (code "94") (name "Net-(U11-DIS)") (class "Default")
      (node (ref "R20") (pin "3") (pinfunction "3_3") (pintype "passive"))
      (node (ref "R21") (pin "2") (pinfunction "2_2") (pintype "passive"))
      (node (ref "U11") (pin "7") (pinfunction "DIS_7") (pintype "input"))
    )
    (net (code "95") (name "Net-(U11-THR)") (class "Default")
      (node (ref "C20") (pin "1") (pinfunction "1_1") (pintype "passive"))
      (node (ref "R21") (pin "3") (pinfunction "3_3") (pintype "passive"))
      (node (ref "U11") (pin "2") (pinfunction "TR_2") (pintype "input"))
      (node (ref "U11") (pin "6") (pinfunction "THR_6") (pintype "input"))
    )
    (net (code "96") (name "VBAT") (class "Default")
      (node (ref "C1") (pin "1") (pinfunction "1_1") (pintype "passive"))
      (node (ref "C14") (pin "1") (pinfunction "1_1") (pintype "passive"))
      (node (ref "C4") (pin "1") (pinfunction "1_1") (pintype "passive"))
      (node (ref "R1") (pin "2") (pinfunction "2_2") (pintype "passive"))
      (node (ref "SW2") (pin "2") (pinfunction "2_2") (pintype "passive"))
      (node (ref "U1") (pin "2") (pinfunction "VIN_2") (pintype "power_in"))
      (node (ref "U1") (pin "3") (pinfunction "EN_3") (pintype "input"))
      (node (ref "U2") (pin "2") (pinfunction "VIN_2") (pintype "power_in"))
      (node (ref "U2") (pin "3") (pinfunction "EN_3") (pintype "input"))
      (node (ref "U3") (pin "12") (pinfunction "VM_12") (pintype "power_in"))
    )
    (net (code "97") (name "unconnected-(JP1-Pad2)") (class "Default")
      (node (ref "JP1") (pin "2") (pinfunction "2_2") (pintype "passive"))
    )
    (net (code "98") (name "unconnected-(JP1-Pad5)") (class "Default")
      (node (ref "JP1") (pin "5") (pinfunction "5_5") (pintype "passive"))
    )
    (net (code "99") (name "unconnected-(JP2-Pad5)") (class "Default")
      (node (ref "JP2") (pin "5") (pinfunction "5_5") (pintype "passive"))
    )
    (net (code "100") (name "unconnected-(JP2-Pad7)") (class "Default")
      (node (ref "JP2") (pin "7") (pinfunction "7_7") (pintype "passive"))
    )
    (net (code "101") (name "unconnected-(JP2-Pad8)") (class "Default")
      (node (ref "JP2") (pin "8") (pinfunction "8_8") (pintype "passive"))
    )
    (net (code "102") (name "unconnected-(JP2-Pad15)") (class "Default")
      (node (ref "JP2") (pin "15") (pinfunction "15_15") (pintype "passive"))
    )
    (net (code "103") (name "unconnected-(R20-Pad1)") (class "Default")
      (node (ref "R20") (pin "1") (pinfunction "1_1") (pintype "passive"))
    )
    (net (code "104") (name "unconnected-(R21-Pad1)") (class "Default")
      (node (ref "R21") (pin "1") (pinfunction "1_1") (pintype "passive"))
    )
    (net (code "105") (name "unconnected-(SW2-Pad1)") (class "Default")
      (node (ref "SW2") (pin "1") (pinfunction "1_1") (pintype "passive"))
    )
    (net (code "106") (name "unconnected-(U1-PG-Pad5)") (class "Default")
      (node (ref "U1") (pin "5") (pinfunction "PG_5") (pintype "output"))
    )
    (net (code "107") (name "unconnected-(U2-PG-Pad5)") (class "Default")
      (node (ref "U2") (pin "5") (pinfunction "PG_5") (pintype "output"))
    )
    (net (code "108") (name "unconnected-(U3-NFAULT-Pad8)") (class "Default")
      (node (ref "U3") (pin "8") (pinfunction "NFAULT_8") (pintype "output"))
    )
    (net (code "109") (name "unconnected-(U5-AUX_CL-Pad7)") (class "Default")
      (node (ref "U5") (pin "7") (pinfunction "AUX_CL_7") (pintype "bidirectional"))
    )
    (net (code "110") (name "unconnected-(U5-AUX_DA-Pad6)") (class "Default")
      (node (ref "U5") (pin "6") (pinfunction "AUX_DA_6") (pintype "bidirectional"))
    )
    (net (code "111") (name "unconnected-(U5-CLKIN-Pad1)") (class "Default")
      (node (ref "U5") (pin "1") (pinfunction "CLKIN_1") (pintype "bidirectional"))
    )
    (net (code "112") (name "unconnected-(U5-CLKOUT-Pad22)") (class "Default")
      (node (ref "U5") (pin "22") (pinfunction "CLKOUT_22") (pintype "bidirectional"))
    )
    (net (code "113") (name "unconnected-(U5-INT-Pad12)") (class "Default")
      (node (ref "U5") (pin "12") (pinfunction "INT_12") (pintype "bidirectional"))
    )
    (net (code "114") (name "unconnected-(U7-AREF-Pad20)") (class "Default")
      (node (ref "U7") (pin "20") (pinfunction "AREF_20") (pintype "passive"))
    )
  )
)
